# CONTROL_circuit_LED_for_Junction_Box.net
KiCad netlist of a schematic drawn in EAGLE
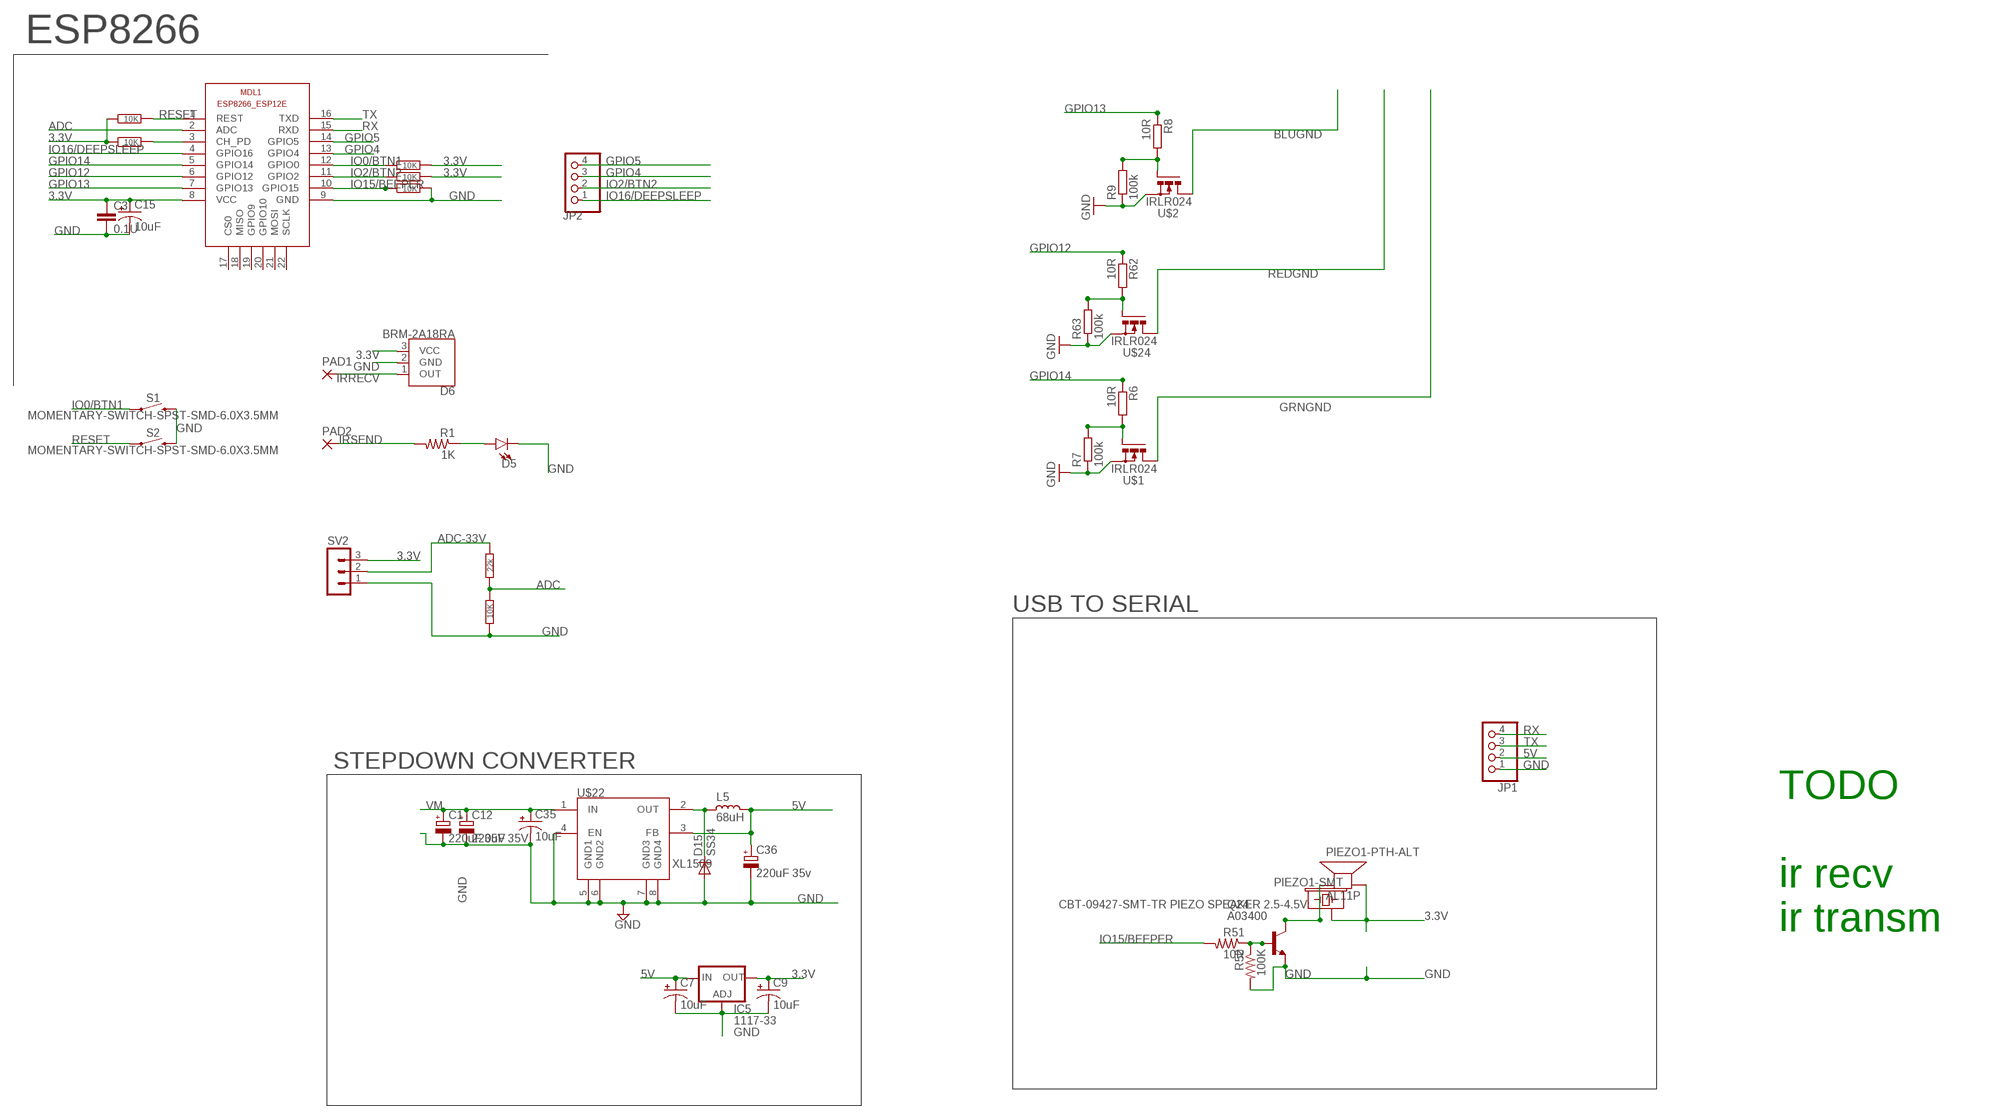
[diagram p0: schematic, sheet 1]

(export (version "E")
  (design (tool "Eeschema 10.0.6"))
  (components
    (comp (ref "C1")
      (value "220uF 35V")
      (footprint "eagle-import:E3,5-8")
      (libsource (lib "eagle-import") (part "CPOL-EUE3.5-8"))
    )
    (comp (ref "C3")
      (value "0.1U")
      (footprint "eagle-import:C1206")
      (libsource (lib "eagle-import") (part "C-EUC1206"))
    )
    (comp (ref "C7")
      (value "10uF")
      (footprint "eagle-import:EIA3216")
      (libsource (lib "eagle-import") (part "CAP_POL1206"))
    )
    (comp (ref "C9")
      (value "10uF")
      (footprint "eagle-import:EIA3216")
      (libsource (lib "eagle-import") (part "CAP_POL1206"))
    )
    (comp (ref "C12")
      (value "220uF 35V")
      (footprint "eagle-import:E3,5-8")
      (libsource (lib "eagle-import") (part "CPOL-EUE3.5-8"))
    )
    (comp (ref "C15")
      (value "10uF")
      (footprint "eagle-import:EIA3216")
      (libsource (lib "eagle-import") (part "CAP_POL1206"))
    )
    (comp (ref "C35")
      (value "10uF")
      (footprint "eagle-import:EIA3216")
      (libsource (lib "eagle-import") (part "CAP_POL1206"))
    )
    (comp (ref "C36")
      (value "220uF 35v")
      (footprint "eagle-import:E3,5-8")
      (libsource (lib "eagle-import") (part "CPOL-EUE3.5-8"))
    )
    (comp (ref "D5")
      (value "LED3MM")
      (footprint "eagle-import:LED_3MM")
      (libsource (lib "eagle-import") (part "LED3MM"))
    )
    (comp (ref "D6")
      (value "BRM-2A18RA")
      (footprint "eagle-import:BRM-2508")
      (libsource (lib "eagle-import") (part "BRM-2A18RA"))
    )
    (comp (ref "D15")
      (value "SS34")
      (footprint "eagle-import:DO-214AC")
      (libsource (lib "eagle-import") (part "DIODE-DO-214AC"))
    )
    (comp (ref "IC5")
      (value "1117-33")
      (footprint "eagle-import:SOT223")
      (libsource (lib "eagle-import") (part "LD117A?S33TR"))
    )
    (comp (ref "JP1")
      (value "PINHD-1X4")
      (footprint "eagle-import:1X04")
      (libsource (lib "eagle-import") (part "PINHD-1X4"))
    )
    (comp (ref "JP2")
      (value "PINHD-1X4")
      (footprint "eagle-import:1X04")
      (libsource (lib "eagle-import") (part "PINHD-1X4"))
    )
    (comp (ref "L5")
      (value "68uH")
      (footprint "eagle-import:CD75")
      (libsource (lib "eagle-import") (part "L_CD75"))
    )
    (comp (ref "MDL1")
      (value "ESP8266-12EESP8266-ESP12E")
      (footprint "eagle-import:ESP8266-ESP12E")
      (libsource (lib "eagle-import") (part "ESP8266-12EESP8266-ESP12E"))
    )
    (comp (ref "PAD1")
      (value "1,6/0,9")
      (footprint "eagle-import:1,6_0,9")
      (libsource (lib "eagle-import") (part "1,6/0,9"))
    )
    (comp (ref "PAD2")
      (value "1,6/0,9")
      (footprint "eagle-import:1,6_0,9")
      (libsource (lib "eagle-import") (part "1,6/0,9"))
    )
    (comp (ref "PIEZO1-PTH-ALT")
      (value "AL11P")
      (footprint "eagle-import:AL11P")
      (libsource (lib "eagle-import") (part "SPEAKER/AL11P"))
    )
    (comp (ref "PIEZO1-SMT")
      (value "CBT-09427-SMT-TR PIEZO SPEAKER 2.5-4.5V")
      (footprint "eagle-import:BUZZER-CCV")
      (libsource (lib "eagle-import") (part "BUZZER-SMD"))
    )
    (comp (ref "Q24")
      (value "A03400")
      (footprint "eagle-import:SOT23-BEC")
      (libsource (lib "eagle-import") (part "BC849SMD"))
    )
    (comp (ref "R1")
      (value "1K")
      (footprint "eagle-import:M1206")
      (libsource (lib "eagle-import") (part "R-US_M1206"))
    )
    (comp (ref "R3")
      (value "22k")
      (footprint "eagle-import:R1206")
      (libsource (lib "eagle-import") (part "R-EU_R1206"))
    )
    (comp (ref "R4")
      (value "10K")
      (footprint "eagle-import:R1206")
      (libsource (lib "eagle-import") (part "R-EU_R1206"))
    )
    (comp (ref "R6")
      (value "10R")
      (footprint "eagle-import:R1206")
      (libsource (lib "eagle-import") (part "resistor_R-EU_R1206"))
    )
    (comp (ref "R7")
      (value "100k")
      (footprint "eagle-import:R1206")
      (libsource (lib "eagle-import") (part "resistor_R-EU_R1206"))
    )
    (comp (ref "R8")
      (value "10R")
      (footprint "eagle-import:R1206")
      (libsource (lib "eagle-import") (part "resistor_R-EU_R1206"))
    )
    (comp (ref "R9")
      (value "100k")
      (footprint "eagle-import:R1206")
      (libsource (lib "eagle-import") (part "resistor_R-EU_R1206"))
    )
    (comp (ref "R11")
      (value "10K")
      (footprint "eagle-import:R1206")
      (libsource (lib "eagle-import") (part "R-EU_R1206"))
    )
    (comp (ref "R12")
      (value "10K")
      (footprint "eagle-import:R1206")
      (libsource (lib "eagle-import") (part "R-EU_R1206"))
    )
    (comp (ref "R28")
      (value "10K")
      (footprint "eagle-import:R1206")
      (libsource (lib "eagle-import") (part "R-EU_R1206"))
    )
    (comp (ref "R29")
      (value "10K")
      (footprint "eagle-import:R1206")
      (libsource (lib "eagle-import") (part "R-EU_R1206"))
    )
    (comp (ref "R31")
      (value "10K")
      (footprint "eagle-import:R1206")
      (libsource (lib "eagle-import") (part "R-EU_R1206"))
    )
    (comp (ref "R51")
      (value "10R")
      (footprint "eagle-import:R1206")
      (libsource (lib "eagle-import") (part "R-US_R1206"))
    )
    (comp (ref "R52")
      (value "100K")
      (footprint "eagle-import:R1206")
      (libsource (lib "eagle-import") (part "R-US_R1206"))
    )
    (comp (ref "R62")
      (value "10R")
      (footprint "eagle-import:R1206")
      (libsource (lib "eagle-import") (part "resistor_R-EU_R1206"))
    )
    (comp (ref "R63")
      (value "100k")
      (footprint "eagle-import:R1206")
      (libsource (lib "eagle-import") (part "resistor_R-EU_R1206"))
    )
    (comp (ref "S1")
      (value "MOMENTARY-SWITCH-SPST-SMD-6.0X3.5MM")
      (footprint "eagle-import:TACTILE_SWITCH_SMD_6.0X3.5MM")
      (libsource (lib "eagle-import") (part "MOMENTARY-SWITCH-SPST-SMD-6.0X3.5MM"))
    )
    (comp (ref "S2")
      (value "MOMENTARY-SWITCH-SPST-SMD-6.0X3.5MM")
      (footprint "eagle-import:TACTILE_SWITCH_SMD_6.0X3.5MM")
      (libsource (lib "eagle-import") (part "MOMENTARY-SWITCH-SPST-SMD-6.0X3.5MM"))
    )
    (comp (ref "SV2")
      (value "MA03-1")
      (footprint "eagle-import:MA03-1")
      (libsource (lib "eagle-import") (part "MA03-1"))
    )
    (comp (ref "U$1")
      (value "IRLR024")
      (footprint "eagle-import:D-PAK_TO252AA")
      (libsource (lib "eagle-import") (part "N-POWER-MOSFETDPAK-MOSFET"))
    )
    (comp (ref "U$2")
      (value "IRLR024")
      (footprint "eagle-import:D-PAK_TO252AA")
      (libsource (lib "eagle-import") (part "N-POWER-MOSFETDPAK-MOSFET"))
    )
    (comp (ref "U$22")
      (value "XL1509")
      (footprint "eagle-import:SO08")
      (libsource (lib "eagle-import") (part "XL1509"))
    )
    (comp (ref "U$24")
      (value "IRLR024")
      (footprint "eagle-import:D-PAK_TO252AA")
      (libsource (lib "eagle-import") (part "N-POWER-MOSFETDPAK-MOSFET"))
    )
  )
  (nets
    (net (code "1") (name "/3.3V") (class "Default")
      (node (ref "C15") (pin "A") (pinfunction "+_A") (pintype "passive"))
      (node (ref "C3") (pin "1") (pinfunction "1_1") (pintype "passive"))
      (node (ref "C9") (pin "A") (pinfunction "+_A") (pintype "passive"))
      (node (ref "D6") (pin "3") (pinfunction "VCC_3") (pintype "bidirectional"))
      (node (ref "IC5") (pin "4") (pinfunction "OUT_4") (pintype "passive"))
      (node (ref "MDL1") (pin "8") (pinfunction "VCC_8") (pintype "bidirectional"))
      (node (ref "PIEZO1-PTH-ALT") (pin "-") (pinfunction "-_-") (pintype "passive"))
      (node (ref "PIEZO1-SMT") (pin "+") (pinfunction "1_+") (pintype "passive"))
      (node (ref "R11") (pin "2") (pinfunction "2_2") (pintype "passive"))
      (node (ref "R12") (pin "2") (pinfunction "2_2") (pintype "passive"))
      (node (ref "R28") (pin "1") (pinfunction "1_1") (pintype "passive"))
      (node (ref "R29") (pin "1") (pinfunction "1_1") (pintype "passive"))
      (node (ref "SV2") (pin "3") (pinfunction "3_3") (pintype "passive"))
    )
    (net (code "2") (name "/5V") (class "Default")
      (node (ref "C36") (pin "+") (pinfunction "+_+") (pintype "passive"))
      (node (ref "C7") (pin "A") (pinfunction "+_A") (pintype "passive"))
      (node (ref "IC5") (pin "3") (pinfunction "IN_3") (pintype "input"))
      (node (ref "JP1") (pin "2") (pinfunction "2_2") (pintype "passive"))
      (node (ref "L5") (pin "1") (pinfunction "1_1") (pintype "passive"))
      (node (ref "U$22") (pin "3") (pinfunction "FB_3") (pintype "bidirectional"))
    )
    (net (code "3") (name "/ADC") (class "Default")
      (node (ref "MDL1") (pin "2") (pinfunction "ADC_2") (pintype "bidirectional"))
      (node (ref "R3") (pin "1") (pinfunction "1_1") (pintype "passive"))
      (node (ref "R4") (pin "2") (pinfunction "2_2") (pintype "passive"))
    )
    (net (code "4") (name "/ADC-33V") (class "Default")
      (node (ref "R3") (pin "2") (pinfunction "2_2") (pintype "passive"))
      (node (ref "SV2") (pin "2") (pinfunction "2_2") (pintype "passive"))
    )
    (net (code "5") (name "/BLUGND") (class "Default")
      (node (ref "U$2") (pin "4") (pinfunction "D_4") (pintype "passive"))
    )
    (net (code "6") (name "/GPIO4") (class "Default")
      (node (ref "JP2") (pin "3") (pinfunction "3_3") (pintype "passive"))
      (node (ref "MDL1") (pin "13") (pinfunction "GPIO4_13") (pintype "bidirectional"))
    )
    (net (code "7") (name "/GPIO5") (class "Default")
      (node (ref "JP2") (pin "4") (pinfunction "4_4") (pintype "passive"))
      (node (ref "MDL1") (pin "14") (pinfunction "GPIO5_14") (pintype "bidirectional"))
    )
    (net (code "8") (name "/GPIO12") (class "Default")
      (node (ref "MDL1") (pin "6") (pinfunction "GPIO12_6") (pintype "bidirectional"))
      (node (ref "R62") (pin "1") (pinfunction "1_1") (pintype "passive"))
    )
    (net (code "9") (name "/GPIO13") (class "Default")
      (node (ref "MDL1") (pin "7") (pinfunction "GPIO13_7") (pintype "bidirectional"))
      (node (ref "R8") (pin "1") (pinfunction "1_1") (pintype "passive"))
    )
    (net (code "10") (name "/GPIO14") (class "Default")
      (node (ref "MDL1") (pin "5") (pinfunction "GPIO14_5") (pintype "bidirectional"))
      (node (ref "R6") (pin "1") (pinfunction "1_1") (pintype "passive"))
    )
    (net (code "11") (name "/GRNGND") (class "Default")
      (node (ref "U$1") (pin "4") (pinfunction "D_4") (pintype "passive"))
    )
    (net (code "12") (name "/IO0{slash}BTN1") (class "Default")
      (node (ref "MDL1") (pin "12") (pinfunction "GPIO0_12") (pintype "bidirectional"))
      (node (ref "R12") (pin "1") (pinfunction "1_1") (pintype "passive"))
      (node (ref "S1") (pin "1") (pinfunction "1_1") (pintype "passive"))
    )
    (net (code "13") (name "/IO2{slash}BTN2") (class "Default")
      (node (ref "JP2") (pin "2") (pinfunction "2_2") (pintype "passive"))
      (node (ref "MDL1") (pin "11") (pinfunction "GPIO2_11") (pintype "bidirectional"))
      (node (ref "R11") (pin "1") (pinfunction "1_1") (pintype "passive"))
    )
    (net (code "14") (name "/IO15{slash}BEEPER") (class "Default")
      (node (ref "MDL1") (pin "10") (pinfunction "GPIO15_10") (pintype "bidirectional"))
      (node (ref "R31") (pin "1") (pinfunction "1_1") (pintype "passive"))
      (node (ref "R51") (pin "2") (pinfunction "2_2") (pintype "passive"))
    )
    (net (code "15") (name "/IO16{slash}DEEPSLEEP") (class "Default")
      (node (ref "JP2") (pin "1") (pinfunction "1_1") (pintype "passive"))
      (node (ref "MDL1") (pin "4") (pinfunction "GPIO16_4") (pintype "bidirectional"))
    )
    (net (code "16") (name "/IRRECV") (class "Default")
      (node (ref "D6") (pin "1") (pinfunction "OUT_1") (pintype "bidirectional"))
      (node (ref "PAD1") (pin "1") (pinfunction "P_1") (pintype "passive"))
    )
    (net (code "17") (name "/IRSEND") (class "Default")
      (node (ref "PAD2") (pin "1") (pinfunction "P_1") (pintype "passive"))
      (node (ref "R1") (pin "2") (pinfunction "2_2") (pintype "passive"))
    )
    (net (code "18") (name "/REDGND") (class "Default")
      (node (ref "U$24") (pin "4") (pinfunction "D_4") (pintype "passive"))
    )
    (net (code "19") (name "/RESET") (class "Default")
      (node (ref "MDL1") (pin "1") (pinfunction "REST_1") (pintype "bidirectional"))
      (node (ref "R29") (pin "2") (pinfunction "2_2") (pintype "passive"))
      (node (ref "S2") (pin "1") (pinfunction "1_1") (pintype "passive"))
    )
    (net (code "20") (name "/RX") (class "Default")
      (node (ref "JP1") (pin "4") (pinfunction "4_4") (pintype "passive"))
      (node (ref "MDL1") (pin "15") (pinfunction "RXD_15") (pintype "bidirectional"))
    )
    (net (code "21") (name "/TX") (class "Default")
      (node (ref "JP1") (pin "3") (pinfunction "3_3") (pintype "passive"))
      (node (ref "MDL1") (pin "16") (pinfunction "TXD_16") (pintype "bidirectional"))
    )
    (net (code "22") (name "/VM") (class "Default")
      (node (ref "C1") (pin "+") (pinfunction "+_+") (pintype "passive"))
      (node (ref "C12") (pin "+") (pinfunction "+_+") (pintype "passive"))
      (node (ref "C35") (pin "A") (pinfunction "+_A") (pintype "passive"))
      (node (ref "U$22") (pin "1") (pinfunction "IN_1") (pintype "bidirectional"))
    )
    (net (code "23") (name "GND") (class "Default")
      (node (ref "C1") (pin "-") (pinfunction "-_-") (pintype "passive"))
      (node (ref "C12") (pin "-") (pinfunction "-_-") (pintype "passive"))
      (node (ref "C15") (pin "C") (pinfunction "-_C") (pintype "passive"))
      (node (ref "C3") (pin "2") (pinfunction "2_2") (pintype "passive"))
      (node (ref "C35") (pin "C") (pinfunction "-_C") (pintype "passive"))
      (node (ref "C36") (pin "-") (pinfunction "-_-") (pintype "passive"))
      (node (ref "C7") (pin "C") (pinfunction "-_C") (pintype "passive"))
      (node (ref "C9") (pin "C") (pinfunction "-_C") (pintype "passive"))
      (node (ref "D15") (pin "2") (pinfunction "A_2") (pintype "passive"))
      (node (ref "D5") (pin "K") (pinfunction "C_K") (pintype "passive"))
      (node (ref "D6") (pin "2") (pinfunction "GND_2") (pintype "bidirectional"))
      (node (ref "IC5") (pin "1") (pinfunction "ADJ_1") (pintype "input"))
      (node (ref "JP1") (pin "1") (pinfunction "1_1") (pintype "passive"))
      (node (ref "MDL1") (pin "9") (pinfunction "GND_9") (pintype "bidirectional"))
      (node (ref "Q24") (pin "E") (pinfunction "E_E") (pintype "passive"))
      (node (ref "R31") (pin "2") (pinfunction "2_2") (pintype "passive"))
      (node (ref "R4") (pin "1") (pinfunction "1_1") (pintype "passive"))
      (node (ref "R52") (pin "2") (pinfunction "2_2") (pintype "passive"))
      (node (ref "R63") (pin "1") (pinfunction "1_1") (pintype "passive"))
      (node (ref "R7") (pin "1") (pinfunction "1_1") (pintype "passive"))
      (node (ref "R9") (pin "1") (pinfunction "1_1") (pintype "passive"))
      (node (ref "S1") (pin "2") (pinfunction "2_2") (pintype "passive"))
      (node (ref "S2") (pin "2") (pinfunction "2_2") (pintype "passive"))
      (node (ref "SV2") (pin "1") (pinfunction "1_1") (pintype "passive"))
      (node (ref "U$1") (pin "3") (pinfunction "S_3") (pintype "passive"))
      (node (ref "U$2") (pin "3") (pinfunction "S_3") (pintype "passive"))
      (node (ref "U$22") (pin "4") (pinfunction "EN_4") (pintype "bidirectional"))
      (node (ref "U$22") (pin "5") (pinfunction "GND1_5") (pintype "bidirectional"))
      (node (ref "U$22") (pin "6") (pinfunction "GND2_6") (pintype "bidirectional"))
      (node (ref "U$22") (pin "7") (pinfunction "GND3_7") (pintype "bidirectional"))
      (node (ref "U$22") (pin "8") (pinfunction "GND4_8") (pintype "bidirectional"))
      (node (ref "U$24") (pin "3") (pinfunction "S_3") (pintype "passive"))
    )
    (net (code "24") (name "Net-(D5-PadA)") (class "Default")
      (node (ref "D5") (pin "A") (pinfunction "A_A") (pintype "passive"))
      (node (ref "R1") (pin "1") (pinfunction "1_1") (pintype "passive"))
    )
    (net (code "25") (name "Net-(D15-C)") (class "Default")
      (node (ref "D15") (pin "1") (pinfunction "C_1") (pintype "passive"))
      (node (ref "L5") (pin "2") (pinfunction "2_2") (pintype "passive"))
      (node (ref "U$22") (pin "2") (pinfunction "OUT_2") (pintype "bidirectional"))
    )
    (net (code "26") (name "Net-(MDL1-CH_PD)") (class "Default")
      (node (ref "MDL1") (pin "3") (pinfunction "CH_PD_3") (pintype "bidirectional"))
      (node (ref "R28") (pin "2") (pinfunction "2_2") (pintype "passive"))
    )
    (net (code "27") (name "Net-(PIEZO1-SMT-2)") (class "Default")
      (node (ref "PIEZO1-PTH-ALT") (pin "+") (pinfunction "+_+") (pintype "passive"))
      (node (ref "PIEZO1-SMT") (pin "-") (pinfunction "2_-") (pintype "passive"))
      (node (ref "Q24") (pin "C") (pinfunction "C_C") (pintype "passive"))
    )
    (net (code "28") (name "Net-(Q24-PadB)") (class "Default")
      (node (ref "Q24") (pin "B") (pinfunction "B_B") (pintype "passive"))
      (node (ref "R51") (pin "1") (pinfunction "1_1") (pintype "passive"))
      (node (ref "R52") (pin "1") (pinfunction "1_1") (pintype "passive"))
    )
    (net (code "29") (name "Net-(U$1-G)") (class "Default")
      (node (ref "R6") (pin "2") (pinfunction "2_2") (pintype "passive"))
      (node (ref "R7") (pin "2") (pinfunction "2_2") (pintype "passive"))
      (node (ref "U$1") (pin "1") (pinfunction "G_1") (pintype "passive"))
    )
    (net (code "30") (name "Net-(U$2-G)") (class "Default")
      (node (ref "R8") (pin "2") (pinfunction "2_2") (pintype "passive"))
      (node (ref "R9") (pin "2") (pinfunction "2_2") (pintype "passive"))
      (node (ref "U$2") (pin "1") (pinfunction "G_1") (pintype "passive"))
    )
    (net (code "31") (name "Net-(U$24-G)") (class "Default")
      (node (ref "R62") (pin "2") (pinfunction "2_2") (pintype "passive"))
      (node (ref "R63") (pin "2") (pinfunction "2_2") (pintype "passive"))
      (node (ref "U$24") (pin "1") (pinfunction "G_1") (pintype "passive"))
    )
    (net (code "32") (name "unconnected-(MDL1-CS0-Pad17)") (class "Default")
      (node (ref "MDL1") (pin "17") (pinfunction "CS0_17") (pintype "bidirectional"))
    )
    (net (code "33") (name "unconnected-(MDL1-GPIO9-Pad19)") (class "Default")
      (node (ref "MDL1") (pin "19") (pinfunction "GPIO9_19") (pintype "bidirectional"))
    )
    (net (code "34") (name "unconnected-(MDL1-GPIO10-Pad20)") (class "Default")
      (node (ref "MDL1") (pin "20") (pinfunction "GPIO10_20") (pintype "bidirectional"))
    )
    (net (code "35") (name "unconnected-(MDL1-MISO-Pad18)") (class "Default")
      (node (ref "MDL1") (pin "18") (pinfunction "MISO_18") (pintype "bidirectional"))
    )
    (net (code "36") (name "unconnected-(MDL1-MOSI-Pad21)") (class "Default")
      (node (ref "MDL1") (pin "21") (pinfunction "MOSI_21") (pintype "bidirectional"))
    )
    (net (code "37") (name "unconnected-(MDL1-SCLK-Pad22)") (class "Default")
      (node (ref "MDL1") (pin "22") (pinfunction "SCLK_22") (pintype "bidirectional"))
    )
  )
)
